# RoverGyro.net
KiCad netlist of a schematic drawn in EAGLE
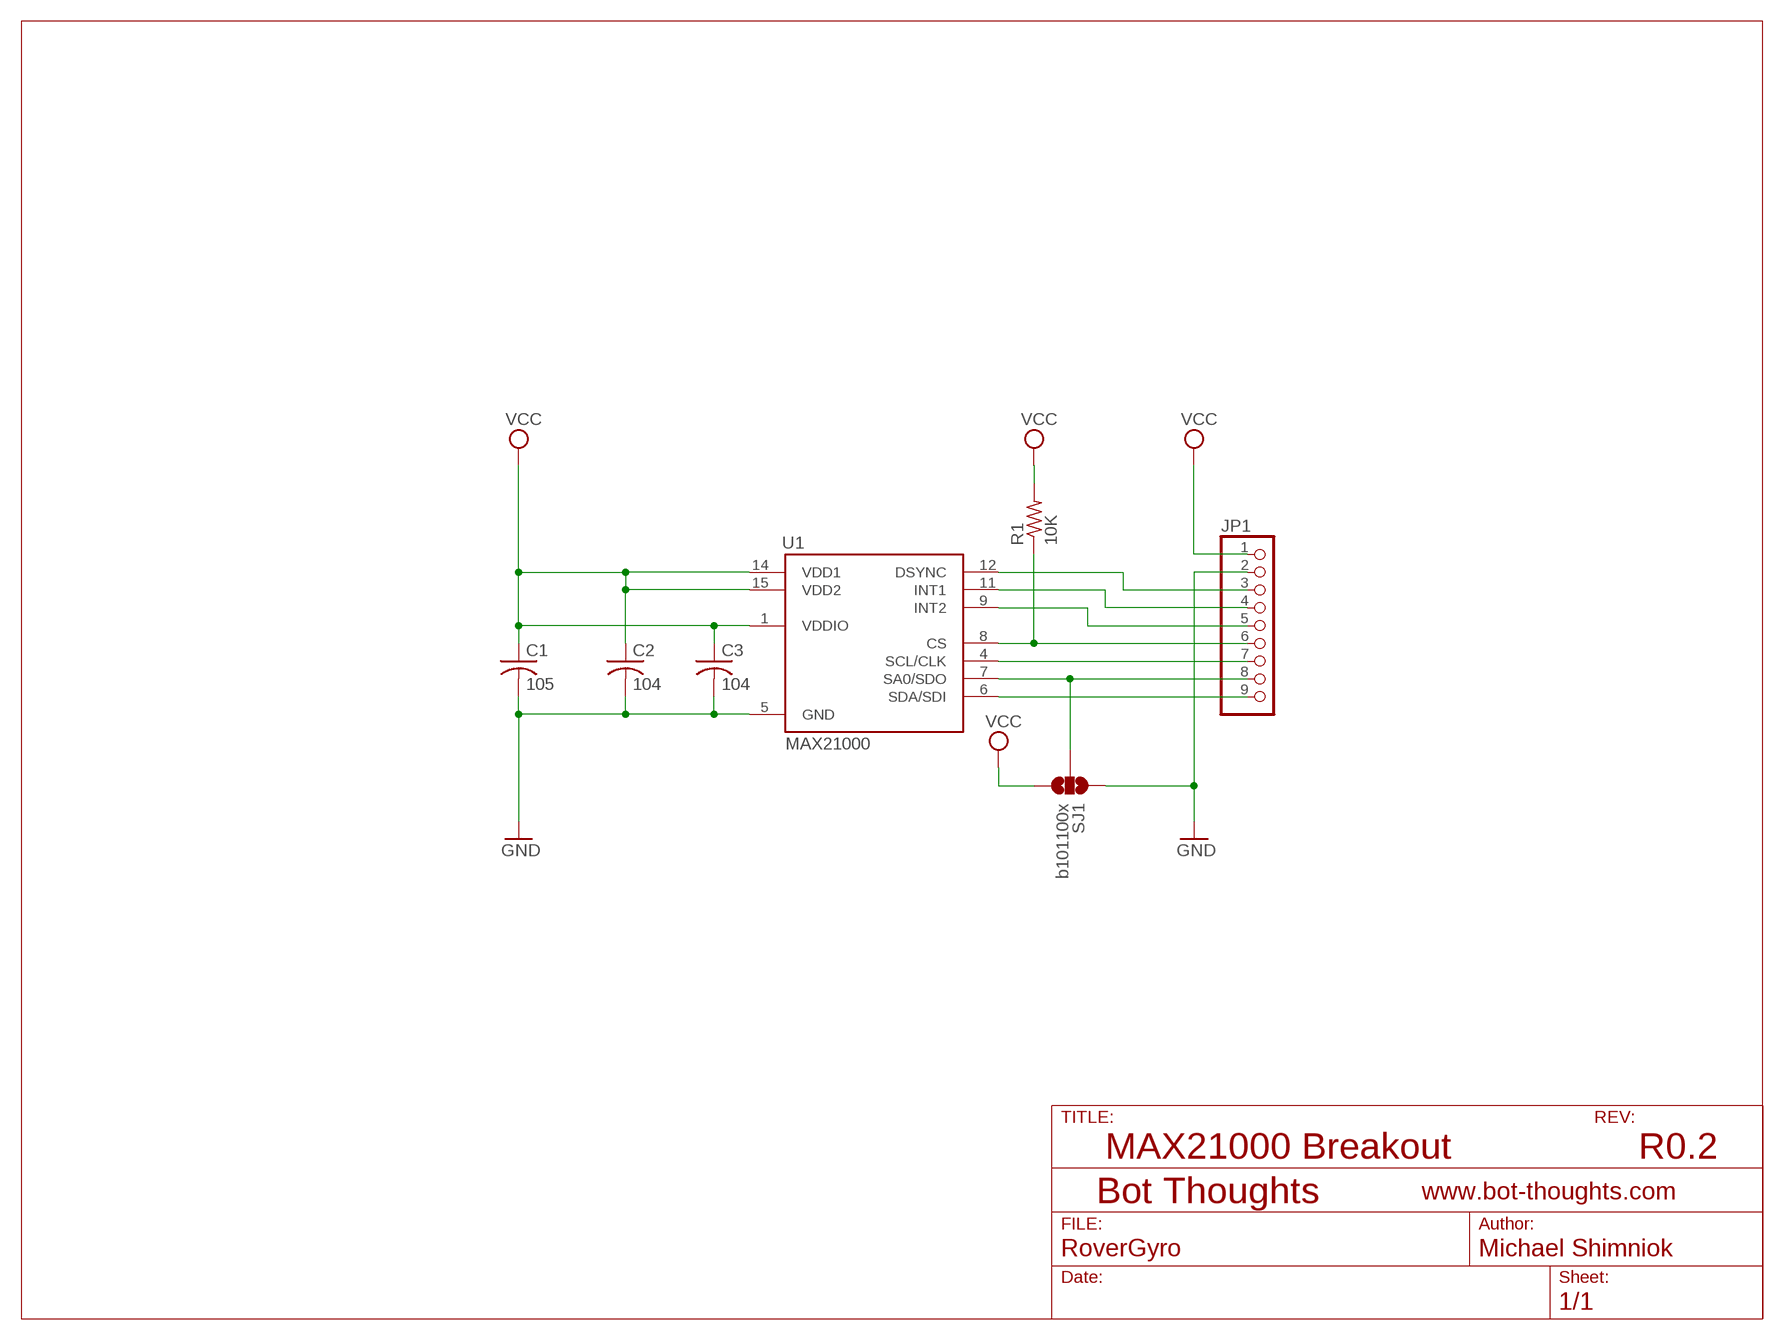
[diagram p0: schematic, sheet 1]

(export (version "E")
  (design (tool "Eeschema 10.0.6"))
  (components
    (comp (ref "C1")
      (value "105")
      (footprint "eagle-import:C0603")
      (libsource (lib "eagle-import") (part "C-USC0603"))
    )
    (comp (ref "C2")
      (value "104")
      (footprint "eagle-import:C0603")
      (libsource (lib "eagle-import") (part "C-USC0603"))
    )
    (comp (ref "C3")
      (value "104")
      (footprint "eagle-import:C0603")
      (libsource (lib "eagle-import") (part "C-USC0603"))
    )
    (comp (ref "JP1")
      (value "PINHD-1X09_2.54-S")
      (footprint "eagle-import:1X09-S")
      (libsource (lib "eagle-import") (part "PINHD-1X09_2.54-S"))
    )
    (comp (ref "R1")
      (value "10K")
      (footprint "eagle-import:R0603")
      (libsource (lib "eagle-import") (part "R-US_R0603"))
    )
    (comp (ref "SJ1")
      (value "b101100x")
      (footprint "eagle-import:SJ_3")
      (libsource (lib "eagle-import") (part "SOLDERJUMPER_2WAYS"))
    )
    (comp (ref "U1")
      (value "MAX21000")
      (footprint "eagle-import:16LGA")
      (libsource (lib "eagle-import") (part "MAX21000"))
    )
  )
  (nets
    (net (code "1") (name "GND") (class "Default")
      (node (ref "C1") (pin "2") (pinfunction "2_2") (pintype "passive"))
      (node (ref "C2") (pin "2") (pinfunction "2_2") (pintype "passive"))
      (node (ref "C3") (pin "2") (pinfunction "2_2") (pintype "passive"))
      (node (ref "JP1") (pin "2") (pinfunction "2_2") (pintype "passive"))
      (node (ref "SJ1") (pin "1") (pinfunction "1_1") (pintype "passive"))
      (node (ref "U1") (pin "5") (pinfunction "GND_5") (pintype "bidirectional"))
    )
    (net (code "2") (name "Net-(U1-CS)") (class "Default")
      (node (ref "JP1") (pin "6") (pinfunction "6_6") (pintype "passive"))
      (node (ref "R1") (pin "1") (pinfunction "1_1") (pintype "passive"))
      (node (ref "U1") (pin "8") (pinfunction "CS_8") (pintype "bidirectional"))
    )
    (net (code "3") (name "Net-(U1-DSYNC)") (class "Default")
      (node (ref "JP1") (pin "3") (pinfunction "3_3") (pintype "passive"))
      (node (ref "U1") (pin "12") (pinfunction "DSYNC_12") (pintype "bidirectional"))
    )
    (net (code "4") (name "Net-(U1-INT1)") (class "Default")
      (node (ref "JP1") (pin "4") (pinfunction "4_4") (pintype "passive"))
      (node (ref "U1") (pin "11") (pinfunction "INT1_11") (pintype "bidirectional"))
    )
    (net (code "5") (name "Net-(U1-INT2)") (class "Default")
      (node (ref "JP1") (pin "5") (pinfunction "5_5") (pintype "passive"))
      (node (ref "U1") (pin "9") (pinfunction "INT2_9") (pintype "bidirectional"))
    )
    (net (code "6") (name "Net-(U1-SA0{slash}SDO)") (class "Default")
      (node (ref "JP1") (pin "8") (pinfunction "8_8") (pintype "passive"))
      (node (ref "SJ1") (pin "2") (pinfunction "2_2") (pintype "passive"))
      (node (ref "U1") (pin "7") (pinfunction "SA0/SDO_7") (pintype "bidirectional"))
    )
    (net (code "7") (name "Net-(U1-SCL{slash}CLK)") (class "Default")
      (node (ref "JP1") (pin "7") (pinfunction "7_7") (pintype "passive"))
      (node (ref "U1") (pin "4") (pinfunction "SCL/CLK_4") (pintype "bidirectional"))
    )
    (net (code "8") (name "Net-(U1-SDA{slash}SDI)") (class "Default")
      (node (ref "JP1") (pin "9") (pinfunction "9_9") (pintype "passive"))
      (node (ref "U1") (pin "6") (pinfunction "SDA/SDI_6") (pintype "bidirectional"))
    )
    (net (code "9") (name "VCC") (class "Default")
      (node (ref "C1") (pin "1") (pinfunction "1_1") (pintype "passive"))
      (node (ref "C2") (pin "1") (pinfunction "1_1") (pintype "passive"))
      (node (ref "C3") (pin "1") (pinfunction "1_1") (pintype "passive"))
      (node (ref "JP1") (pin "1") (pinfunction "1_1") (pintype "passive"))
      (node (ref "R1") (pin "2") (pinfunction "2_2") (pintype "passive"))
      (node (ref "SJ1") (pin "3") (pinfunction "3_3") (pintype "passive"))
      (node (ref "U1") (pin "1") (pinfunction "VDDIO_1") (pintype "bidirectional"))
      (node (ref "U1") (pin "14") (pinfunction "VDD1_14") (pintype "bidirectional"))
      (node (ref "U1") (pin "15") (pinfunction "VDD2_15") (pintype "bidirectional"))
    )
  )
)
